# mobo_v0_2_6-20-18.net
KiCad netlist of a schematic drawn in EAGLE
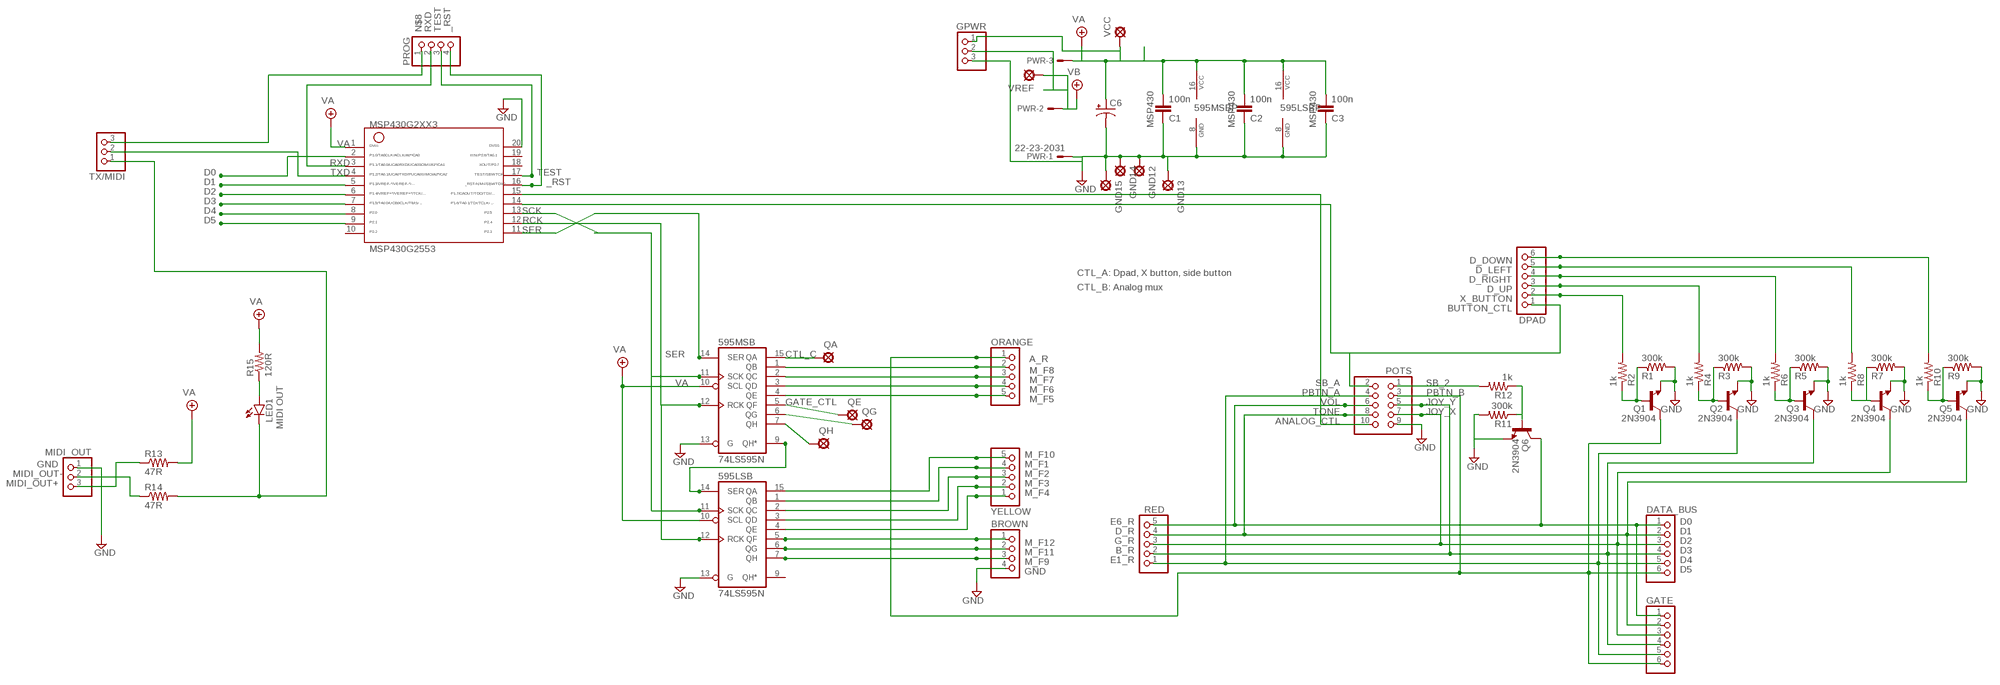
[diagram p0: schematic, sheet 1]

(export (version "E")
  (design (tool "Eeschema 10.0.6"))
  (components
    (comp (ref "595LSB")
      (value "74LS595N")
      (footprint "eagle-import:DIL16")
      (libsource (lib "eagle-import") (part "74595NLS"))
    )
    (comp (ref "595MSB")
      (value "74LS595N")
      (footprint "eagle-import:DIL16")
      (libsource (lib "eagle-import") (part "74595NLS"))
    )
    (comp (ref "BROWN")
      (value "PINHD-1X4")
      (footprint "eagle-import:1X04")
      (libsource (lib "eagle-import") (part "PINHD-1X4"))
    )
    (comp (ref "C1")
      (value "100n")
      (footprint "eagle-import:050X030_050_3")
      (libsource (lib "eagle-import") (part "050X030_050"))
    )
    (comp (ref "C2")
      (value "100n")
      (footprint "eagle-import:050X030_050_1")
      (libsource (lib "eagle-import") (part "050X030_0501"))
    )
    (comp (ref "C3")
      (value "100n")
      (footprint "eagle-import:050X030_050_1")
      (libsource (lib "eagle-import") (part "050X030_0501"))
    )
    (comp (ref "C6")
      (value "0501")
      (footprint "eagle-import:050_020_1")
      (libsource (lib "eagle-import") (part "0501"))
    )
    (comp (ref "DATA_BUS")
      (value "PINHD-1X6")
      (footprint "eagle-import:1X06")
      (libsource (lib "eagle-import") (part "PINHD-1X6"))
    )
    (comp (ref "DPAD")
      (value "PINHD-1X6")
      (footprint "eagle-import:1X06")
      (libsource (lib "eagle-import") (part "PINHD-1X6"))
    )
    (comp (ref "GATE")
      (value "PINHD-1X6")
      (footprint "eagle-import:1X06")
      (libsource (lib "eagle-import") (part "PINHD-1X6"))
    )
    (comp (ref "GND12")
      (value "PAD")
      (footprint "eagle-import:SQUARE")
      (libsource (lib "eagle-import") (part "PAD"))
    )
    (comp (ref "GND13")
      (value "PAD")
      (footprint "eagle-import:SQUARE")
      (libsource (lib "eagle-import") (part "PAD"))
    )
    (comp (ref "GND14")
      (value "PAD")
      (footprint "eagle-import:SQUARE")
      (libsource (lib "eagle-import") (part "PAD"))
    )
    (comp (ref "GND15")
      (value "PAD")
      (footprint "eagle-import:SQUARE")
      (libsource (lib "eagle-import") (part "PAD"))
    )
    (comp (ref "GPWR")
      (value "PINHD-1X3")
      (footprint "eagle-import:1X03")
      (libsource (lib "eagle-import") (part "PINHD-1X3"))
    )
    (comp (ref "LED1")
      (value "LED3MM")
      (footprint "eagle-import:LED3MM")
      (libsource (lib "eagle-import") (part "LED3MM"))
    )
    (comp (ref "MIDI_OUT")
      (value "PINHD-1X3")
      (footprint "eagle-import:1X03")
      (libsource (lib "eagle-import") (part "PINHD-1X3"))
    )
    (comp (ref "MSP430G2553")
      (value "G2XX3---N20")
      (footprint "eagle-import:N20")
      (libsource (lib "eagle-import") (part "G2XX3---N20"))
    )
    (comp (ref "ORANGE")
      (value "PINHD-1X5")
      (footprint "eagle-import:1X05")
      (libsource (lib "eagle-import") (part "PINHD-1X5"))
    )
    (comp (ref "POTS")
      (value "PINHD-2X5IDC")
      (footprint "eagle-import:10PIN_IDC")
      (libsource (lib "eagle-import") (part "PINHD-2X5IDC"))
    )
    (comp (ref "PROG")
      (value "PINHD-1X4")
      (footprint "eagle-import:1X04")
      (libsource (lib "eagle-import") (part "PINHD-1X4"))
    )
    (comp (ref "PWR")
      (value "22-23-2031")
      (footprint "eagle-import:22-23-2031")
      (fields (field (name "MF") "MOLEX"))
      (libsource (lib "eagle-import") (part "22-23-2031"))
    )
    (comp (ref "Q1")
      (value "2N3904")
      (footprint "eagle-import:TO92-")
      (libsource (lib "eagle-import") (part "2N3904"))
    )
    (comp (ref "Q2")
      (value "2N3904")
      (footprint "eagle-import:TO92-")
      (libsource (lib "eagle-import") (part "2N3904"))
    )
    (comp (ref "Q3")
      (value "2N3904")
      (footprint "eagle-import:TO92-")
      (libsource (lib "eagle-import") (part "2N3904"))
    )
    (comp (ref "Q4")
      (value "2N3904")
      (footprint "eagle-import:TO92-")
      (libsource (lib "eagle-import") (part "2N3904"))
    )
    (comp (ref "Q5")
      (value "2N3904")
      (footprint "eagle-import:TO92-")
      (libsource (lib "eagle-import") (part "2N3904"))
    )
    (comp (ref "Q6")
      (value "2N3904")
      (footprint "eagle-import:TO92-")
      (libsource (lib "eagle-import") (part "2N3904"))
    )
    (comp (ref "QA")
      (value "PAD")
      (footprint "eagle-import:SQUARE")
      (libsource (lib "eagle-import") (part "PAD"))
    )
    (comp (ref "QE")
      (value "PAD")
      (footprint "eagle-import:SQUARE")
      (libsource (lib "eagle-import") (part "PAD"))
    )
    (comp (ref "QG")
      (value "PAD")
      (footprint "eagle-import:SQUARE")
      (libsource (lib "eagle-import") (part "PAD"))
    )
    (comp (ref "QH")
      (value "PAD")
      (footprint "eagle-import:SQUARE")
      (libsource (lib "eagle-import") (part "PAD"))
    )
    (comp (ref "R1")
      (value "300k")
      (footprint "eagle-import:R0207_3")
      (libsource (lib "eagle-import") (part "6MM.3"))
    )
    (comp (ref "R2")
      (value "1k")
      (footprint "eagle-import:R0207_3")
      (libsource (lib "eagle-import") (part "6MM.3"))
    )
    (comp (ref "R3")
      (value "300k")
      (footprint "eagle-import:R0207_3")
      (libsource (lib "eagle-import") (part "6MM.3"))
    )
    (comp (ref "R4")
      (value "1k")
      (footprint "eagle-import:R0207_3")
      (libsource (lib "eagle-import") (part "6MM.3"))
    )
    (comp (ref "R5")
      (value "300k")
      (footprint "eagle-import:R0207_3")
      (libsource (lib "eagle-import") (part "6MM.3"))
    )
    (comp (ref "R6")
      (value "1k")
      (footprint "eagle-import:R0207_3")
      (libsource (lib "eagle-import") (part "6MM.3"))
    )
    (comp (ref "R7")
      (value "300k")
      (footprint "eagle-import:R0207_3")
      (libsource (lib "eagle-import") (part "6MM.3"))
    )
    (comp (ref "R8")
      (value "1k")
      (footprint "eagle-import:R0207_3")
      (libsource (lib "eagle-import") (part "6MM.3"))
    )
    (comp (ref "R9")
      (value "300k")
      (footprint "eagle-import:R0207_3")
      (libsource (lib "eagle-import") (part "6MM.3"))
    )
    (comp (ref "R10")
      (value "1k")
      (footprint "eagle-import:R0207_3")
      (libsource (lib "eagle-import") (part "6MM.3"))
    )
    (comp (ref "R11")
      (value "300k")
      (footprint "eagle-import:R0207_3")
      (libsource (lib "eagle-import") (part "6MM.3"))
    )
    (comp (ref "R12")
      (value "1k")
      (footprint "eagle-import:R0207_3")
      (libsource (lib "eagle-import") (part "6MM.3"))
    )
    (comp (ref "R13")
      (value "47R")
      (footprint "eagle-import:R0207_3")
      (libsource (lib "eagle-import") (part "6MM.3"))
    )
    (comp (ref "R14")
      (value "47R")
      (footprint "eagle-import:R0207_3")
      (libsource (lib "eagle-import") (part "6MM.3"))
    )
    (comp (ref "R15")
      (value "120R")
      (footprint "eagle-import:R0207_3")
      (libsource (lib "eagle-import") (part "6MM.3"))
    )
    (comp (ref "RED")
      (value "PINHD-1X5")
      (footprint "eagle-import:1X05")
      (libsource (lib "eagle-import") (part "PINHD-1X5"))
    )
    (comp (ref "TX/MIDI")
      (value "PINHD-1X3")
      (footprint "eagle-import:1X03")
      (libsource (lib "eagle-import") (part "PINHD-1X3"))
    )
    (comp (ref "VCC")
      (value "PAD")
      (footprint "eagle-import:SQUARE")
      (libsource (lib "eagle-import") (part "PAD"))
    )
    (comp (ref "VREF")
      (value "PAD")
      (footprint "eagle-import:SQUARE")
      (libsource (lib "eagle-import") (part "PAD"))
    )
    (comp (ref "YELLOW")
      (value "PINHD-1X5")
      (footprint "eagle-import:1X05")
      (libsource (lib "eagle-import") (part "PINHD-1X5"))
    )
  )
  (nets
    (net (code "1") (name "/ANALOG_CTL") (class "Default")
      (node (ref "MSP430G2553") (pin "15") (pinfunction "15_15") (pintype "bidirectional"))
      (node (ref "POTS") (pin "10") (pinfunction "10_10") (pintype "passive"))
    )
    (net (code "2") (name "/BUTTON_CTL") (class "Default")
      (node (ref "DPAD") (pin "1") (pinfunction "1_1") (pintype "passive"))
      (node (ref "MSP430G2553") (pin "14") (pinfunction "14_14") (pintype "bidirectional"))
      (node (ref "POTS") (pin "2") (pinfunction "2_2") (pintype "passive"))
    )
    (net (code "3") (name "/CTL_C") (class "Default")
      (node (ref "595MSB") (pin "15") (pinfunction "QA_15") (pintype "tri_state"))
      (node (ref "QA") (pin "1") (pinfunction "PAD_1") (pintype "passive"))
    )
    (net (code "4") (name "/D0") (class "Default")
      (node (ref "DATA_BUS") (pin "1") (pinfunction "1_1") (pintype "passive"))
      (node (ref "GATE") (pin "1") (pinfunction "1_1") (pintype "passive"))
      (node (ref "MSP430G2553") (pin "2") (pinfunction "2_2") (pintype "bidirectional"))
      (node (ref "POTS") (pin "6") (pinfunction "6_6") (pintype "passive"))
      (node (ref "Q6") (pin "1") (pinfunction "C_1") (pintype "passive"))
      (node (ref "RED") (pin "5") (pinfunction "5_5") (pintype "passive"))
    )
    (net (code "5") (name "/D1") (class "Default")
      (node (ref "DATA_BUS") (pin "2") (pinfunction "2_2") (pintype "passive"))
      (node (ref "GATE") (pin "2") (pinfunction "2_2") (pintype "passive"))
      (node (ref "MSP430G2553") (pin "5") (pinfunction "5_5") (pintype "bidirectional"))
      (node (ref "POTS") (pin "8") (pinfunction "8_8") (pintype "passive"))
      (node (ref "Q5") (pin "1") (pinfunction "C_1") (pintype "passive"))
      (node (ref "RED") (pin "4") (pinfunction "4_4") (pintype "passive"))
    )
    (net (code "6") (name "/D2") (class "Default")
      (node (ref "DATA_BUS") (pin "3") (pinfunction "3_3") (pintype "passive"))
      (node (ref "GATE") (pin "3") (pinfunction "3_3") (pintype "passive"))
      (node (ref "MSP430G2553") (pin "6") (pinfunction "6_6") (pintype "bidirectional"))
      (node (ref "POTS") (pin "7") (pinfunction "7_7") (pintype "passive"))
      (node (ref "Q4") (pin "1") (pinfunction "C_1") (pintype "passive"))
      (node (ref "RED") (pin "3") (pinfunction "3_3") (pintype "passive"))
    )
    (net (code "7") (name "/D3") (class "Default")
      (node (ref "DATA_BUS") (pin "4") (pinfunction "4_4") (pintype "passive"))
      (node (ref "GATE") (pin "4") (pinfunction "4_4") (pintype "passive"))
      (node (ref "MSP430G2553") (pin "7") (pinfunction "7_7") (pintype "bidirectional"))
      (node (ref "POTS") (pin "5") (pinfunction "5_5") (pintype "passive"))
      (node (ref "Q3") (pin "1") (pinfunction "C_1") (pintype "passive"))
      (node (ref "RED") (pin "2") (pinfunction "2_2") (pintype "passive"))
    )
    (net (code "8") (name "/D4") (class "Default")
      (node (ref "DATA_BUS") (pin "5") (pinfunction "5_5") (pintype "passive"))
      (node (ref "GATE") (pin "5") (pinfunction "5_5") (pintype "passive"))
      (node (ref "MSP430G2553") (pin "8") (pinfunction "8_8") (pintype "bidirectional"))
      (node (ref "POTS") (pin "4") (pinfunction "4_4") (pintype "passive"))
      (node (ref "Q2") (pin "1") (pinfunction "C_1") (pintype "passive"))
      (node (ref "RED") (pin "1") (pinfunction "1_1") (pintype "passive"))
    )
    (net (code "9") (name "/D5") (class "Default")
      (node (ref "DATA_BUS") (pin "6") (pinfunction "6_6") (pintype "passive"))
      (node (ref "GATE") (pin "6") (pinfunction "6_6") (pintype "passive"))
      (node (ref "MSP430G2553") (pin "9") (pinfunction "9_9") (pintype "bidirectional"))
      (node (ref "ORANGE") (pin "1") (pinfunction "1_1") (pintype "passive"))
      (node (ref "POTS") (pin "3") (pinfunction "3_3") (pintype "passive"))
      (node (ref "Q1") (pin "1") (pinfunction "C_1") (pintype "passive"))
    )
    (net (code "10") (name "/D_DOWN") (class "Default")
      (node (ref "DPAD") (pin "6") (pinfunction "6_6") (pintype "passive"))
      (node (ref "R10") (pin "2") (pinfunction "2_2") (pintype "passive"))
    )
    (net (code "11") (name "/D_LEFT") (class "Default")
      (node (ref "DPAD") (pin "5") (pinfunction "5_5") (pintype "passive"))
      (node (ref "R8") (pin "2") (pinfunction "2_2") (pintype "passive"))
    )
    (net (code "12") (name "/D_RIGHT") (class "Default")
      (node (ref "DPAD") (pin "4") (pinfunction "4_4") (pintype "passive"))
      (node (ref "R6") (pin "2") (pinfunction "2_2") (pintype "passive"))
    )
    (net (code "13") (name "/D_UP") (class "Default")
      (node (ref "DPAD") (pin "3") (pinfunction "3_3") (pintype "passive"))
      (node (ref "R4") (pin "2") (pinfunction "2_2") (pintype "passive"))
    )
    (net (code "14") (name "/GATE_CTL") (class "Default")
      (node (ref "595MSB") (pin "5") (pinfunction "QF_5") (pintype "tri_state"))
      (node (ref "QE") (pin "1") (pinfunction "PAD_1") (pintype "passive"))
    )
    (net (code "15") (name "/MIDI_OUT+") (class "Default")
      (node (ref "MIDI_OUT") (pin "3") (pinfunction "3_3") (pintype "passive"))
      (node (ref "R13") (pin "1") (pinfunction "1_1") (pintype "passive"))
    )
    (net (code "16") (name "/MIDI_OUT-") (class "Default")
      (node (ref "MIDI_OUT") (pin "2") (pinfunction "2_2") (pintype "passive"))
      (node (ref "R14") (pin "1") (pinfunction "1_1") (pintype "passive"))
    )
    (net (code "17") (name "/M_F1") (class "Default")
      (node (ref "595LSB") (pin "1") (pinfunction "QB_1") (pintype "tri_state"))
      (node (ref "YELLOW") (pin "4") (pinfunction "4_4") (pintype "passive"))
    )
    (net (code "18") (name "/M_F2") (class "Default")
      (node (ref "595LSB") (pin "2") (pinfunction "QC_2") (pintype "tri_state"))
      (node (ref "YELLOW") (pin "3") (pinfunction "3_3") (pintype "passive"))
    )
    (net (code "19") (name "/M_F3") (class "Default")
      (node (ref "595LSB") (pin "3") (pinfunction "QD_3") (pintype "tri_state"))
      (node (ref "YELLOW") (pin "2") (pinfunction "2_2") (pintype "passive"))
    )
    (net (code "20") (name "/M_F4") (class "Default")
      (node (ref "595LSB") (pin "4") (pinfunction "QE_4") (pintype "tri_state"))
      (node (ref "YELLOW") (pin "1") (pinfunction "1_1") (pintype "passive"))
    )
    (net (code "21") (name "/M_F5") (class "Default")
      (node (ref "595MSB") (pin "4") (pinfunction "QE_4") (pintype "tri_state"))
      (node (ref "ORANGE") (pin "5") (pinfunction "5_5") (pintype "passive"))
    )
    (net (code "22") (name "/M_F6") (class "Default")
      (node (ref "595MSB") (pin "3") (pinfunction "QD_3") (pintype "tri_state"))
      (node (ref "ORANGE") (pin "4") (pinfunction "4_4") (pintype "passive"))
    )
    (net (code "23") (name "/M_F7") (class "Default")
      (node (ref "595MSB") (pin "2") (pinfunction "QC_2") (pintype "tri_state"))
      (node (ref "ORANGE") (pin "3") (pinfunction "3_3") (pintype "passive"))
    )
    (net (code "24") (name "/M_F8") (class "Default")
      (node (ref "595MSB") (pin "1") (pinfunction "QB_1") (pintype "tri_state"))
      (node (ref "ORANGE") (pin "2") (pinfunction "2_2") (pintype "passive"))
    )
    (net (code "25") (name "/M_F9") (class "Default")
      (node (ref "595LSB") (pin "7") (pinfunction "QH_7") (pintype "tri_state"))
      (node (ref "BROWN") (pin "3") (pinfunction "3_3") (pintype "passive"))
    )
    (net (code "26") (name "/M_F10") (class "Default")
      (node (ref "595LSB") (pin "15") (pinfunction "QA_15") (pintype "tri_state"))
      (node (ref "YELLOW") (pin "5") (pinfunction "5_5") (pintype "passive"))
    )
    (net (code "27") (name "/M_F11") (class "Default")
      (node (ref "595LSB") (pin "6") (pinfunction "QG_6") (pintype "tri_state"))
      (node (ref "BROWN") (pin "2") (pinfunction "2_2") (pintype "passive"))
    )
    (net (code "28") (name "/M_F12") (class "Default")
      (node (ref "595LSB") (pin "5") (pinfunction "QF_5") (pintype "tri_state"))
      (node (ref "BROWN") (pin "1") (pinfunction "1_1") (pintype "passive"))
    )
    (net (code "29") (name "/N$8") (class "Default")
      (node (ref "PROG") (pin "1") (pinfunction "1_1") (pintype "passive"))
      (node (ref "TX/MIDI") (pin "3") (pinfunction "3_3") (pintype "passive"))
    )
    (net (code "30") (name "/RCK") (class "Default")
      (node (ref "595LSB") (pin "12") (pinfunction "RCK_12") (pintype "input"))
      (node (ref "595MSB") (pin "12") (pinfunction "RCK_12") (pintype "input"))
      (node (ref "MSP430G2553") (pin "12") (pinfunction "12_12") (pintype "bidirectional"))
    )
    (net (code "31") (name "/RXD") (class "Default")
      (node (ref "MSP430G2553") (pin "3") (pinfunction "3_3") (pintype "bidirectional"))
      (node (ref "PROG") (pin "2") (pinfunction "2_2") (pintype "passive"))
    )
    (net (code "32") (name "/SB_2") (class "Default")
      (node (ref "POTS") (pin "1") (pinfunction "1_1") (pintype "passive"))
      (node (ref "R12") (pin "2") (pinfunction "2_2") (pintype "passive"))
    )
    (net (code "33") (name "/SCK") (class "Default")
      (node (ref "595LSB") (pin "11") (pinfunction "SCK_11") (pintype "input"))
      (node (ref "595MSB") (pin "11") (pinfunction "SCK_11") (pintype "input"))
      (node (ref "MSP430G2553") (pin "13") (pinfunction "13_13") (pintype "bidirectional"))
    )
    (net (code "34") (name "/SER") (class "Default")
      (node (ref "595MSB") (pin "14") (pinfunction "SER_14") (pintype "input"))
      (node (ref "MSP430G2553") (pin "11") (pinfunction "11_11") (pintype "bidirectional"))
    )
    (net (code "35") (name "/TEST") (class "Default")
      (node (ref "MSP430G2553") (pin "17") (pinfunction "17_17") (pintype "bidirectional"))
      (node (ref "PROG") (pin "3") (pinfunction "3_3") (pintype "passive"))
    )
    (net (code "36") (name "/TXD") (class "Default")
      (node (ref "MSP430G2553") (pin "4") (pinfunction "4_4") (pintype "bidirectional"))
      (node (ref "TX/MIDI") (pin "2") (pinfunction "2_2") (pintype "passive"))
    )
    (net (code "37") (name "/X_BUTTON") (class "Default")
      (node (ref "DPAD") (pin "2") (pinfunction "2_2") (pintype "passive"))
      (node (ref "R2") (pin "2") (pinfunction "2_2") (pintype "passive"))
    )
    (net (code "38") (name "/_RST") (class "Default")
      (node (ref "MSP430G2553") (pin "16") (pinfunction "16_16") (pintype "bidirectional"))
      (node (ref "PROG") (pin "4") (pinfunction "4_4") (pintype "passive"))
    )
    (net (code "39") (name "GND") (class "Default")
      (node (ref "595LSB") (pin "13") (pinfunction "G_13") (pintype "input"))
      (node (ref "595LSB") (pin "8") (pinfunction "GND_8") (pintype "power_in"))
      (node (ref "595MSB") (pin "13") (pinfunction "G_13") (pintype "input"))
      (node (ref "595MSB") (pin "8") (pinfunction "GND_8") (pintype "power_in"))
      (node (ref "BROWN") (pin "4") (pinfunction "4_4") (pintype "passive"))
      (node (ref "C1") (pin "1") (pinfunction "1_1") (pintype "passive"))
      (node (ref "C2") (pin "1") (pinfunction "1_1") (pintype "passive"))
      (node (ref "C3") (pin "1") (pinfunction "1_1") (pintype "passive"))
      (node (ref "C6") (pin "-") (pinfunction "-_-") (pintype "passive"))
      (node (ref "GND12") (pin "1") (pinfunction "PAD_1") (pintype "passive"))
      (node (ref "GND13") (pin "1") (pinfunction "PAD_1") (pintype "passive"))
      (node (ref "GND14") (pin "1") (pinfunction "PAD_1") (pintype "passive"))
      (node (ref "GND15") (pin "1") (pinfunction "PAD_1") (pintype "passive"))
      (node (ref "GPWR") (pin "3") (pinfunction "3_3") (pintype "passive"))
      (node (ref "MIDI_OUT") (pin "1") (pinfunction "1_1") (pintype "passive"))
      (node (ref "MSP430G2553") (pin "20") (pinfunction "20_20") (pintype "bidirectional"))
      (node (ref "POTS") (pin "9") (pinfunction "9_9") (pintype "passive"))
      (node (ref "PWR") (pin "1") (pinfunction "S_1") (pintype "passive"))
      (node (ref "Q1") (pin "3") (pinfunction "E_3") (pintype "passive"))
      (node (ref "Q2") (pin "3") (pinfunction "E_3") (pintype "passive"))
      (node (ref "Q3") (pin "3") (pinfunction "E_3") (pintype "passive"))
      (node (ref "Q4") (pin "3") (pinfunction "E_3") (pintype "passive"))
      (node (ref "Q5") (pin "3") (pinfunction "E_3") (pintype "passive"))
      (node (ref "Q6") (pin "3") (pinfunction "E_3") (pintype "passive"))
      (node (ref "R1") (pin "2") (pinfunction "2_2") (pintype "passive"))
      (node (ref "R11") (pin "2") (pinfunction "2_2") (pintype "passive"))
      (node (ref "R3") (pin "2") (pinfunction "2_2") (pintype "passive"))
      (node (ref "R5") (pin "2") (pinfunction "2_2") (pintype "passive"))
      (node (ref "R7") (pin "2") (pinfunction "2_2") (pintype "passive"))
      (node (ref "R9") (pin "2") (pinfunction "2_2") (pintype "passive"))
    )
    (net (code "40") (name "Net-(595LSBA-SER)") (class "Default")
      (node (ref "595LSB") (pin "14") (pinfunction "SER_14") (pintype "input"))
      (node (ref "595MSB") (pin "9") (pinfunction "QH*_9") (pintype "tri_state"))
    )
    (net (code "41") (name "Net-(595MSBA-QG)") (class "Default")
      (node (ref "595MSB") (pin "6") (pinfunction "QG_6") (pintype "tri_state"))
      (node (ref "QG") (pin "1") (pinfunction "PAD_1") (pintype "passive"))
    )
    (net (code "42") (name "Net-(595MSBA-QH)") (class "Default")
      (node (ref "595MSB") (pin "7") (pinfunction "QH_7") (pintype "tri_state"))
      (node (ref "QH") (pin "1") (pinfunction "PAD_1") (pintype "passive"))
    )
    (net (code "43") (name "Net-(LED1-C)") (class "Default")
      (node (ref "LED1") (pin "K") (pinfunction "C_K") (pintype "passive"))
      (node (ref "R14") (pin "2") (pinfunction "2_2") (pintype "passive"))
      (node (ref "TX/MIDI") (pin "1") (pinfunction "1_1") (pintype "passive"))
    )
    (net (code "44") (name "Net-(LED1-PadA)") (class "Default")
      (node (ref "LED1") (pin "A") (pinfunction "A_A") (pintype "passive"))
      (node (ref "R15") (pin "1") (pinfunction "1_1") (pintype "passive"))
    )
    (net (code "45") (name "Net-(Q1-B)") (class "Default")
      (node (ref "Q1") (pin "2") (pinfunction "B_2") (pintype "passive"))
      (node (ref "R1") (pin "1") (pinfunction "1_1") (pintype "passive"))
      (node (ref "R2") (pin "1") (pinfunction "1_1") (pintype "passive"))
    )
    (net (code "46") (name "Net-(Q2-B)") (class "Default")
      (node (ref "Q2") (pin "2") (pinfunction "B_2") (pintype "passive"))
      (node (ref "R3") (pin "1") (pinfunction "1_1") (pintype "passive"))
      (node (ref "R4") (pin "1") (pinfunction "1_1") (pintype "passive"))
    )
    (net (code "47") (name "Net-(Q3-B)") (class "Default")
      (node (ref "Q3") (pin "2") (pinfunction "B_2") (pintype "passive"))
      (node (ref "R5") (pin "1") (pinfunction "1_1") (pintype "passive"))
      (node (ref "R6") (pin "1") (pinfunction "1_1") (pintype "passive"))
    )
    (net (code "48") (name "Net-(Q4-B)") (class "Default")
      (node (ref "Q4") (pin "2") (pinfunction "B_2") (pintype "passive"))
      (node (ref "R7") (pin "1") (pinfunction "1_1") (pintype "passive"))
      (node (ref "R8") (pin "1") (pinfunction "1_1") (pintype "passive"))
    )
    (net (code "49") (name "Net-(Q5-B)") (class "Default")
      (node (ref "Q5") (pin "2") (pinfunction "B_2") (pintype "passive"))
      (node (ref "R10") (pin "1") (pinfunction "1_1") (pintype "passive"))
      (node (ref "R9") (pin "1") (pinfunction "1_1") (pintype "passive"))
    )
    (net (code "50") (name "Net-(Q6-B)") (class "Default")
      (node (ref "Q6") (pin "2") (pinfunction "B_2") (pintype "passive"))
      (node (ref "R11") (pin "1") (pinfunction "1_1") (pintype "passive"))
      (node (ref "R12") (pin "1") (pinfunction "1_1") (pintype "passive"))
    )
    (net (code "51") (name "VA") (class "Default")
      (node (ref "595LSB") (pin "10") (pinfunction "SCL_10") (pintype "input"))
      (node (ref "595LSB") (pin "16") (pinfunction "VCC_16") (pintype "power_in"))
      (node (ref "595MSB") (pin "10") (pinfunction "SCL_10") (pintype "input"))
      (node (ref "595MSB") (pin "16") (pinfunction "VCC_16") (pintype "power_in"))
      (node (ref "C1") (pin "2") (pinfunction "2_2") (pintype "passive"))
      (node (ref "C2") (pin "2") (pinfunction "2_2") (pintype "passive"))
      (node (ref "C3") (pin "2") (pinfunction "2_2") (pintype "passive"))
      (node (ref "C6") (pin "+") (pinfunction "+_+") (pintype "passive"))
      (node (ref "GPWR") (pin "1") (pinfunction "1_1") (pintype "passive"))
      (node (ref "MSP430G2553") (pin "1") (pinfunction "1_1") (pintype "bidirectional"))
      (node (ref "PWR") (pin "3") (pinfunction "S_3") (pintype "passive"))
      (node (ref "R13") (pin "2") (pinfunction "2_2") (pintype "passive"))
      (node (ref "R15") (pin "2") (pinfunction "2_2") (pintype "passive"))
      (node (ref "VCC") (pin "1") (pinfunction "PAD_1") (pintype "passive"))
    )
    (net (code "52") (name "VB") (class "Default")
      (node (ref "GPWR") (pin "2") (pinfunction "2_2") (pintype "passive"))
      (node (ref "PWR") (pin "2") (pinfunction "S_2") (pintype "passive"))
      (node (ref "VREF") (pin "1") (pinfunction "PAD_1") (pintype "passive"))
    )
    (net (code "53") (name "unconnected-(595LSBA-QH*-Pad9)") (class "Default")
      (node (ref "595LSB") (pin "9") (pinfunction "QH*_9") (pintype "tri_state"))
    )
    (net (code "54") (name "unconnected-(MSP430G2553-Pad10)") (class "Default")
      (node (ref "MSP430G2553") (pin "10") (pinfunction "10_10") (pintype "bidirectional"))
    )
    (net (code "55") (name "unconnected-(MSP430G2553-Pad18)") (class "Default")
      (node (ref "MSP430G2553") (pin "18") (pinfunction "18_18") (pintype "bidirectional"))
    )
    (net (code "56") (name "unconnected-(MSP430G2553-Pad19)") (class "Default")
      (node (ref "MSP430G2553") (pin "19") (pinfunction "19_19") (pintype "bidirectional"))
    )
  )
)
